# Yukari_3_9150.net
KiCad netlist of a schematic drawn in EAGLE
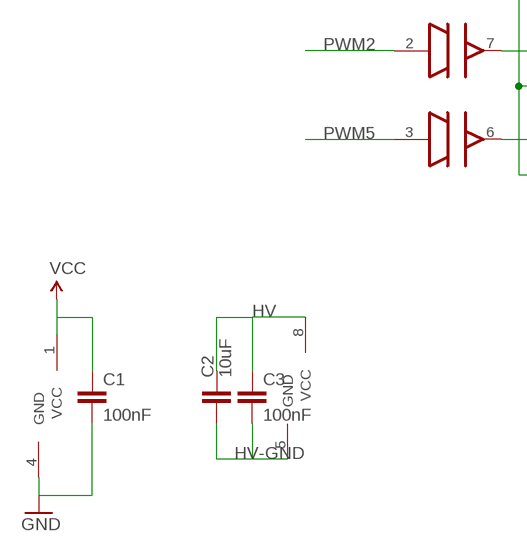
[diagram p0: schematic, sheet 1, part 1 of 2]
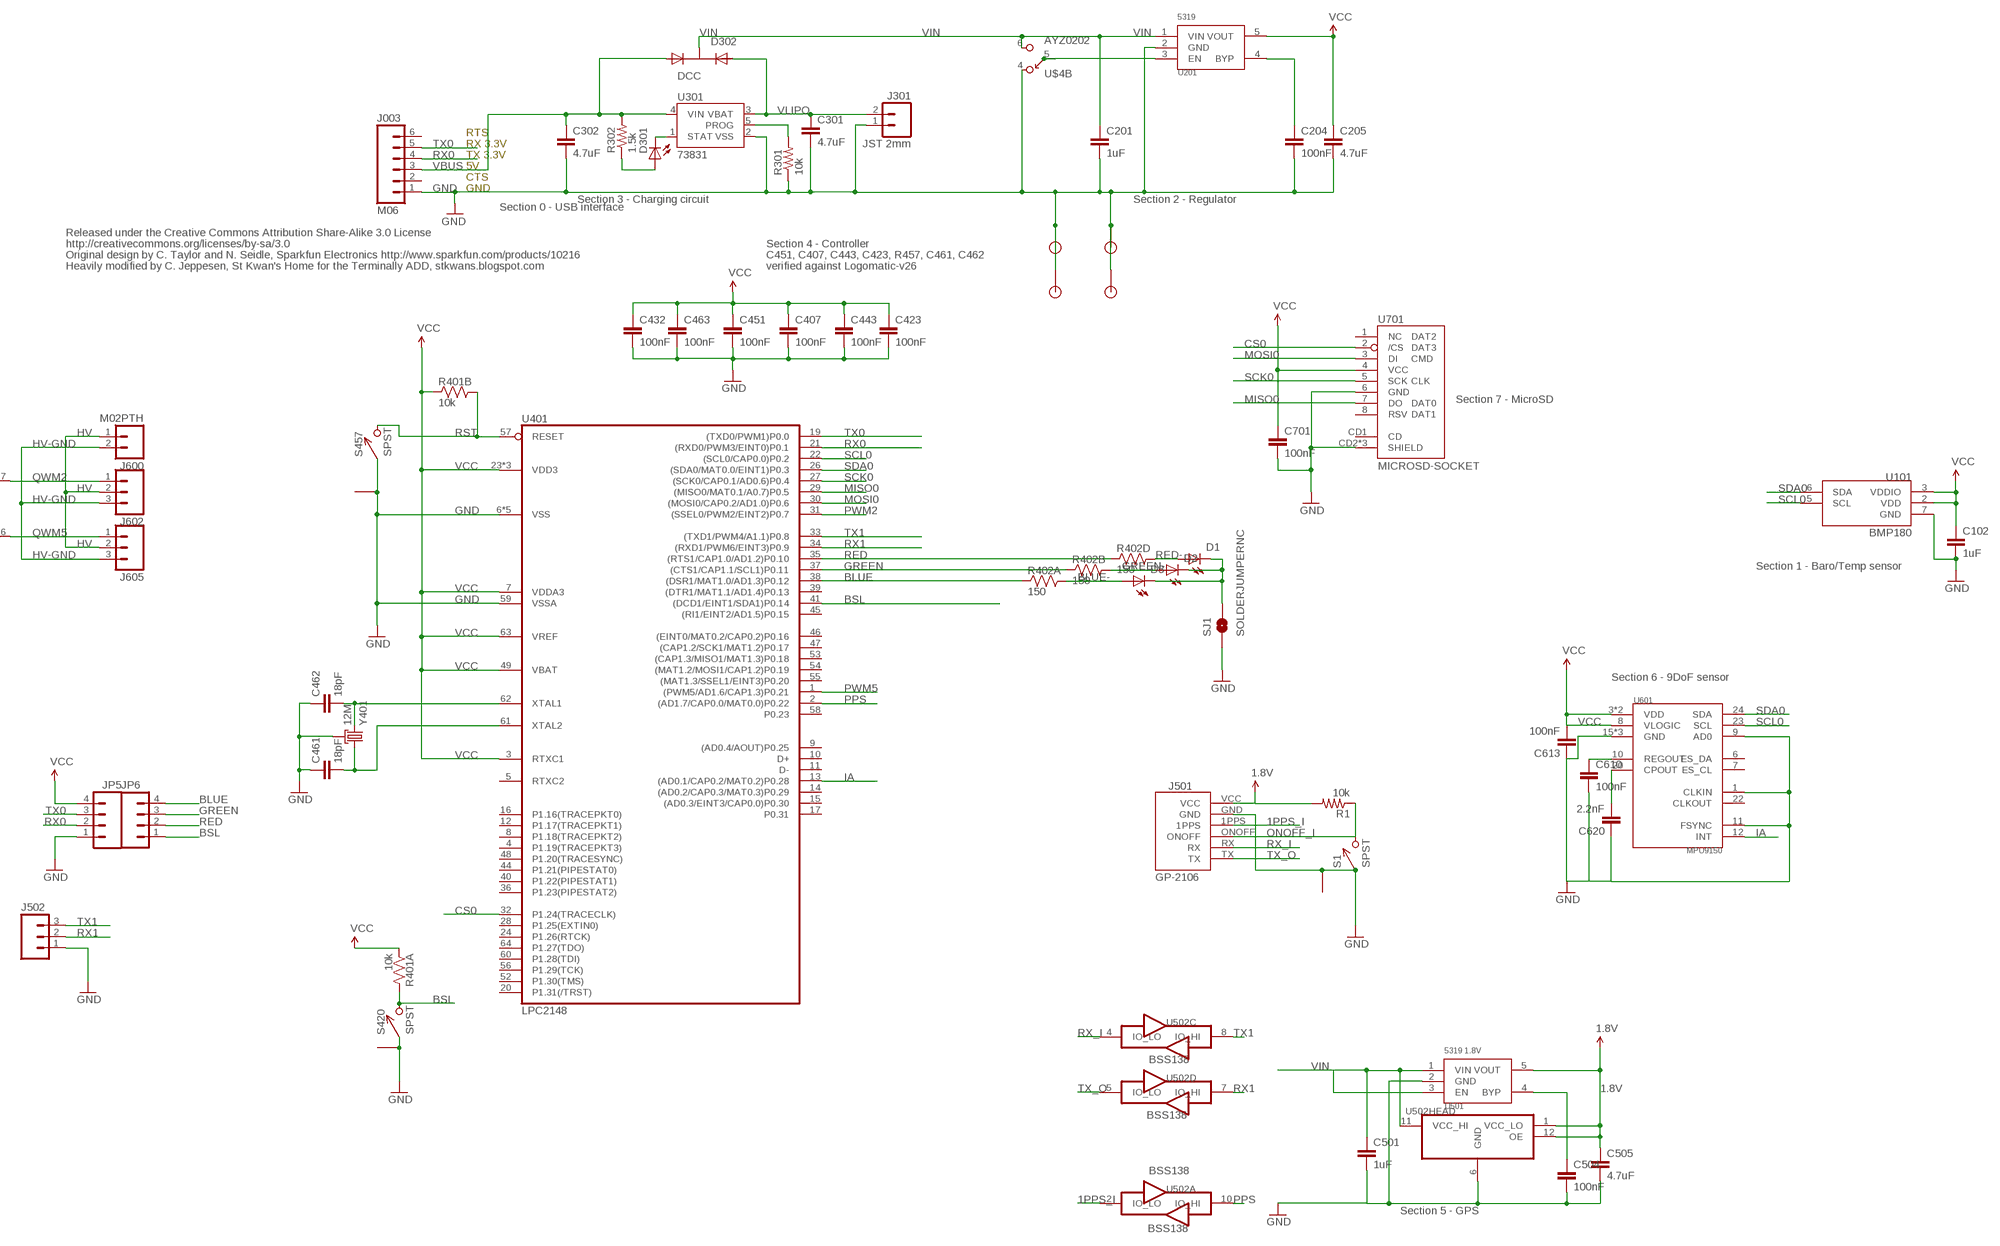
[diagram p1: schematic, sheet 1, part 2 of 2]

(export (version "E")
  (design (tool "Eeschema 10.0.6"))
  (components
    (comp (ref "C1")
      (value "100nF")
      (footprint "eagle-import:0402-CAP")
      (libsource (lib "eagle-import") (part "CAP0402-CAP"))
    )
    (comp (ref "C2")
      (value "10uF")
      (footprint "eagle-import:0603-CAP")
      (libsource (lib "eagle-import") (part "CAP0603-CAP"))
    )
    (comp (ref "C3")
      (value "100nF")
      (footprint "eagle-import:0402-CAP")
      (libsource (lib "eagle-import") (part "CAP0402-CAP"))
    )
    (comp (ref "C102")
      (value "1uF")
      (footprint "eagle-import:0402-CAP")
      (libsource (lib "eagle-import") (part "SparkFun-Passives_CAP0402-CAP"))
    )
    (comp (ref "C201")
      (value "1uF")
      (footprint "eagle-import:0402-CAP")
      (libsource (lib "eagle-import") (part "CAP0402-CAP"))
    )
    (comp (ref "C204")
      (value "100nF")
      (footprint "eagle-import:0402-CAP")
      (libsource (lib "eagle-import") (part "CAP0402-CAP"))
    )
    (comp (ref "C205")
      (value "4.7uF")
      (footprint "eagle-import:0402-CAP")
      (libsource (lib "eagle-import") (part "CAP0402-CAP"))
    )
    (comp (ref "C301")
      (value "4.7uF")
      (footprint "eagle-import:0402-CAP")
      (libsource (lib "eagle-import") (part "CAP0402-CAP"))
    )
    (comp (ref "C302")
      (value "4.7uF")
      (footprint "eagle-import:0402-CAP")
      (libsource (lib "eagle-import") (part "CAP0402-CAP"))
    )
    (comp (ref "C407")
      (value "100nF")
      (footprint "eagle-import:0402-CAP")
      (libsource (lib "eagle-import") (part "CAP0402-CAP"))
    )
    (comp (ref "C423")
      (value "100nF")
      (footprint "eagle-import:0402-CAP")
      (libsource (lib "eagle-import") (part "CAP0402-CAP"))
    )
    (comp (ref "C432")
      (value "100nF")
      (footprint "eagle-import:0402-CAP")
      (libsource (lib "eagle-import") (part "CAP0402-CAP"))
    )
    (comp (ref "C443")
      (value "100nF")
      (footprint "eagle-import:0402-CAP")
      (libsource (lib "eagle-import") (part "CAP0402-CAP"))
    )
    (comp (ref "C451")
      (value "100nF")
      (footprint "eagle-import:0402-CAP")
      (libsource (lib "eagle-import") (part "CAP0402-CAP"))
    )
    (comp (ref "C461")
      (value "18pF")
      (footprint "eagle-import:0402-CAP")
      (libsource (lib "eagle-import") (part "CAP0402-CAP"))
    )
    (comp (ref "C462")
      (value "18pF")
      (footprint "eagle-import:0402-CAP")
      (libsource (lib "eagle-import") (part "CAP0402-CAP"))
    )
    (comp (ref "C463")
      (value "100nF")
      (footprint "eagle-import:0402-CAP")
      (libsource (lib "eagle-import") (part "CAP0402-CAP"))
    )
    (comp (ref "C501")
      (value "1uF")
      (footprint "eagle-import:0402-CAP")
      (libsource (lib "eagle-import") (part "CAP0402-CAP"))
    )
    (comp (ref "C504")
      (value "100nF")
      (footprint "eagle-import:0402-CAP")
      (libsource (lib "eagle-import") (part "CAP0402-CAP"))
    )
    (comp (ref "C505")
      (value "4.7uF")
      (footprint "eagle-import:0402-CAP")
      (libsource (lib "eagle-import") (part "CAP0402-CAP"))
    )
    (comp (ref "C610")
      (value "100nF")
      (footprint "eagle-import:0402-CAP")
      (libsource (lib "eagle-import") (part "SparkFun-Passives_CAP0402-CAP"))
    )
    (comp (ref "C613")
      (value "100nF")
      (footprint "eagle-import:0402-CAP")
      (libsource (lib "eagle-import") (part "SparkFun-Passives_CAP0402-CAP"))
    )
    (comp (ref "C620")
      (value "2.2nF")
      (footprint "eagle-import:0402-CAP")
      (libsource (lib "eagle-import") (part "SparkFun-Passives_CAP0402-CAP"))
    )
    (comp (ref "C701")
      (value "100nF")
      (footprint "eagle-import:0402-CAP")
      (libsource (lib "eagle-import") (part "CAP0402-CAP"))
    )
    (comp (ref "D1")
      (value "RED")
      (footprint "eagle-import:LED-0603")
      (libsource (lib "eagle-import") (part "LED0603"))
    )
    (comp (ref "D2")
      (value "GREEN")
      (footprint "eagle-import:LED-0603")
      (libsource (lib "eagle-import") (part "LED0603"))
    )
    (comp (ref "D3")
      (value "BLUE")
      (footprint "eagle-import:LED-0603")
      (libsource (lib "eagle-import") (part "LED0603"))
    )
    (comp (ref "D301")
      (value "RED")
      (footprint "eagle-import:LED-0603")
      (libsource (lib "eagle-import") (part "LED0603"))
    )
    (comp (ref "D302")
      (value "DCC")
      (footprint "eagle-import:SOT-23-3")
      (libsource (lib "eagle-import") (part "PMEG2005CT"))
    )
    (comp (ref "J003")
      (value "M06")
      (footprint "eagle-import:1X06")
      (libsource (lib "eagle-import") (part "M06SIP"))
    )
    (comp (ref "J301")
      (value "JST 2mm")
      (footprint "eagle-import:JST-2-SMD")
      (libsource (lib "eagle-import") (part "M02-JST-2MM-SMT"))
    )
    (comp (ref "J501")
      (value "GP-2106")
      (footprint "eagle-import:GP-2106")
      (libsource (lib "eagle-import") (part "GP-2106"))
    )
    (comp (ref "J502")
      (value "M03PTH")
      (footprint "eagle-import:1X03")
      (libsource (lib "eagle-import") (part "M03PTH"))
    )
    (comp (ref "J600")
      (value "M02PTH")
      (footprint "eagle-import:1X02")
      (libsource (lib "eagle-import") (part "SparkFun-Connectors_M02PTH"))
    )
    (comp (ref "J602")
      (value "M03PTH")
      (footprint "eagle-import:1X03")
      (libsource (lib "eagle-import") (part "M03PTH"))
    )
    (comp (ref "J605")
      (value "M03PTH")
      (footprint "eagle-import:1X03")
      (libsource (lib "eagle-import") (part "M03PTH"))
    )
    (comp (ref "JP1")
      (value "STANDOFF")
      (footprint "eagle-import:STANDOFF")
      (libsource (lib "eagle-import") (part "STANDOFF"))
    )
    (comp (ref "JP2")
      (value "STANDOFF")
      (footprint "eagle-import:STANDOFF")
      (libsource (lib "eagle-import") (part "STANDOFF"))
    )
    (comp (ref "JP3")
      (value "STANDOFF")
      (footprint "eagle-import:STANDOFF")
      (libsource (lib "eagle-import") (part "STANDOFF"))
    )
    (comp (ref "JP4")
      (value "STANDOFF")
      (footprint "eagle-import:STANDOFF")
      (libsource (lib "eagle-import") (part "STANDOFF"))
    )
    (comp (ref "JP5")
      (value "M04PTH")
      (footprint "eagle-import:1X04")
      (libsource (lib "eagle-import") (part "M04PTH"))
    )
    (comp (ref "JP6")
      (value "M04PTH")
      (footprint "eagle-import:1X04")
      (libsource (lib "eagle-import") (part "M04PTH"))
    )
    (comp (ref "R1")
      (value "10k")
      (footprint "eagle-import:0402-RES")
      (libsource (lib "eagle-import") (part "RESISTOR0402-RES"))
    )
    (comp (ref "R301")
      (value "10k")
      (footprint "eagle-import:0402-RES")
      (libsource (lib "eagle-import") (part "RESISTOR0402-RES"))
    )
    (comp (ref "R302")
      (value "1.5k")
      (footprint "eagle-import:0402-RES")
      (libsource (lib "eagle-import") (part "RESISTOR0402-RES"))
    )
    (comp (ref "R401")
      (value "10k")
      (footprint "eagle-import:CRA02")
      (libsource (lib "eagle-import") (part "RP2EXB24V"))
    )
    (comp (ref "R402")
      (value "150")
      (footprint "eagle-import:CRA04")
      (libsource (lib "eagle-import") (part "RP404"))
    )
    (comp (ref "S1")
      (value "SPST")
      (footprint "eagle-import:B3U-1100P")
      (libsource (lib "eagle-import") (part "B3U-1100P"))
    )
    (comp (ref "S420")
      (value "SPST")
      (footprint "eagle-import:B3U-1100P")
      (libsource (lib "eagle-import") (part "B3U-1100P"))
    )
    (comp (ref "S457")
      (value "SPST")
      (footprint "eagle-import:B3U-1100P")
      (libsource (lib "eagle-import") (part "B3U-1100P"))
    )
    (comp (ref "SJ1")
      (value "SOLDERJUMPERNC")
      (footprint "eagle-import:SJ_2S")
      (libsource (lib "eagle-import") (part "SOLDERJUMPERNC"))
    )
    (comp (ref "U$4")
      (value "AYZ0202")
      (footprint "eagle-import:AYZ0202")
      (libsource (lib "eagle-import") (part "AYZ0202"))
    )
    (comp (ref "U101")
      (value "BMP180")
      (footprint "eagle-import:BMP180")
      (libsource (lib "eagle-import") (part "BMP180"))
    )
    (comp (ref "U201")
      (value "5319")
      (footprint "eagle-import:SOT-23-5")
      (libsource (lib "eagle-import") (part "MIC5319D5"))
    )
    (comp (ref "U301")
      (value "73831")
      (footprint "eagle-import:SOT23-5")
      (libsource (lib "eagle-import") (part "MCP73831"))
    )
    (comp (ref "U401")
      (value "LPC2148")
      (footprint "eagle-import:LQFP64")
      (libsource (lib "eagle-import") (part "LPC2148"))
    )
    (comp (ref "U501")
      (value "5319 1.8V")
      (footprint "eagle-import:SOT-23-5")
      (libsource (lib "eagle-import") (part "MIC5319D5"))
    )
    (comp (ref "U502")
      (value "TXB0104RUT")
      (footprint "eagle-import:R-PUQFN-N12")
      (libsource (lib "eagle-import") (part "TXB0104RUT"))
    )
    (comp (ref "U600")
      (value "ADUM3221")
      (footprint "eagle-import:SO8N")
      (libsource (lib "eagle-import") (part "ADUM3221"))
    )
    (comp (ref "U601")
      (value "MPU9150")
      (footprint "eagle-import:LLGA24")
      (libsource (lib "eagle-import") (part "MPU9150"))
    )
    (comp (ref "U701")
      (value "MICROSD-SOCKET")
      (footprint "eagle-import:MICROSD-SOCKET-PP")
      (libsource (lib "eagle-import") (part "MICROSD-SOCKET"))
    )
    (comp (ref "Y401")
      (value "12M")
      (footprint "eagle-import:CRYSTAL_SMD")
      (libsource (lib "eagle-import") (part "TSX-3225"))
    )
  )
  (nets
    (net (code "1") (name "/1PPS_I") (class "Default")
      (node (ref "J501") (pin "1PPS") (pinfunction "1PPS_1PPS") (pintype "bidirectional"))
      (node (ref "U502") (pin "2") (pinfunction "IO_LO_2") (pintype "bidirectional"))
    )
    (net (code "2") (name "/BLUE") (class "Default")
      (node (ref "JP6") (pin "4") (pinfunction "4_4") (pintype "passive"))
      (node (ref "R402") (pin "1") (pinfunction "1_1") (pintype "passive"))
      (node (ref "U401") (pin "38") (pinfunction "(DSR1/MAT1.0/AD1.3)P0.12_38") (pintype "bidirectional"))
    )
    (net (code "3") (name "/BLUE-") (class "Default")
      (node (ref "D3") (pin "A") (pinfunction "A_A") (pintype "passive"))
      (node (ref "R402") (pin "8") (pinfunction "2_8") (pintype "passive"))
    )
    (net (code "4") (name "/BSL") (class "Default")
      (node (ref "JP6") (pin "1") (pinfunction "1_1") (pintype "passive"))
      (node (ref "R401") (pin "4") (pinfunction "2_4") (pintype "passive"))
      (node (ref "S420") (pin "P$2") (pinfunction "2_P$2") (pintype "bidirectional"))
      (node (ref "U401") (pin "41") (pinfunction "(DCD1/EINT1/SDA1)P0.14_41") (pintype "bidirectional"))
    )
    (net (code "5") (name "/CS0") (class "Default")
      (node (ref "U401") (pin "32") (pinfunction "P1.24(TRACECLK)_32") (pintype "bidirectional"))
      (node (ref "U701") (pin "2") (pinfunction "/CS_2") (pintype "bidirectional"))
    )
    (net (code "6") (name "/GREEN") (class "Default")
      (node (ref "JP6") (pin "3") (pinfunction "3_3") (pintype "passive"))
      (node (ref "R402") (pin "2") (pinfunction "1_2") (pintype "passive"))
      (node (ref "U401") (pin "37") (pinfunction "(CTS1/CAP1.1/SCL1)P0.11_37") (pintype "bidirectional"))
    )
    (net (code "7") (name "/GREEN-") (class "Default")
      (node (ref "D2") (pin "A") (pinfunction "A_A") (pintype "passive"))
      (node (ref "R402") (pin "7") (pinfunction "2_7") (pintype "passive"))
    )
    (net (code "8") (name "/HV") (class "Default")
      (node (ref "C2") (pin "1") (pinfunction "1_1") (pintype "passive"))
      (node (ref "C3") (pin "1") (pinfunction "1_1") (pintype "passive"))
      (node (ref "J600") (pin "1") (pinfunction "1_1") (pintype "passive"))
      (node (ref "J602") (pin "2") (pinfunction "2_2") (pintype "passive"))
      (node (ref "J605") (pin "2") (pinfunction "2_2") (pintype "passive"))
      (node (ref "U600") (pin "8") (pinfunction "VCC_8") (pintype "bidirectional"))
    )
    (net (code "9") (name "/HV-GND") (class "Default")
      (node (ref "C2") (pin "2") (pinfunction "2_2") (pintype "passive"))
      (node (ref "C3") (pin "2") (pinfunction "2_2") (pintype "passive"))
      (node (ref "J600") (pin "2") (pinfunction "2_2") (pintype "passive"))
      (node (ref "J602") (pin "3") (pinfunction "3_3") (pintype "passive"))
      (node (ref "J605") (pin "3") (pinfunction "3_3") (pintype "passive"))
      (node (ref "U600") (pin "5") (pinfunction "GND_5") (pintype "bidirectional"))
    )
    (net (code "10") (name "/IA") (class "Default")
      (node (ref "U401") (pin "13") (pinfunction "(AD0.1/CAP0.2/MAT0.2)P0.28_13") (pintype "bidirectional"))
      (node (ref "U601") (pin "12") (pinfunction "INT_12") (pintype "bidirectional"))
    )
    (net (code "11") (name "/MISO0") (class "Default")
      (node (ref "U401") (pin "29") (pinfunction "(MISO0/MAT0.1/A0.7)P0.5_29") (pintype "bidirectional"))
      (node (ref "U701") (pin "7") (pinfunction "DO_7") (pintype "bidirectional"))
    )
    (net (code "12") (name "/MOSI0") (class "Default")
      (node (ref "U401") (pin "30") (pinfunction "(MOSI0/CAP0.2/AD1.0)P0.6_30") (pintype "bidirectional"))
      (node (ref "U701") (pin "3") (pinfunction "DI_3") (pintype "bidirectional"))
    )
    (net (code "13") (name "/ONOFF_I") (class "Default")
      (node (ref "J501") (pin "ONOFF") (pinfunction "ONOFF_ONOFF") (pintype "bidirectional"))
      (node (ref "R1") (pin "1") (pinfunction "1_1") (pintype "passive"))
      (node (ref "S1") (pin "P$2") (pinfunction "2_P$2") (pintype "bidirectional"))
    )
    (net (code "14") (name "/PPS") (class "Default")
      (node (ref "U401") (pin "2") (pinfunction "(AD1.7/CAP0.0/MAT0.0)P0.22_2") (pintype "bidirectional"))
      (node (ref "U502") (pin "10") (pinfunction "IO_HI_10") (pintype "bidirectional"))
    )
    (net (code "15") (name "/PWM2") (class "Default")
      (node (ref "U401") (pin "31") (pinfunction "(SSEL0/PWM2/EINT2)P0.7_31") (pintype "bidirectional"))
      (node (ref "U600") (pin "2") (pinfunction "IN_2") (pintype "input"))
    )
    (net (code "16") (name "/PWM5") (class "Default")
      (node (ref "U401") (pin "1") (pinfunction "(PWM5/AD1.6/CAP1.3)P0.21_1") (pintype "bidirectional"))
      (node (ref "U600") (pin "3") (pinfunction "IN_3") (pintype "input"))
    )
    (net (code "17") (name "/QWM2") (class "Default")
      (node (ref "J602") (pin "1") (pinfunction "1_1") (pintype "passive"))
      (node (ref "U600") (pin "7") (pinfunction "OUT_7") (pintype "bidirectional"))
    )
    (net (code "18") (name "/QWM5") (class "Default")
      (node (ref "J605") (pin "1") (pinfunction "1_1") (pintype "passive"))
      (node (ref "U600") (pin "6") (pinfunction "OUT_6") (pintype "bidirectional"))
    )
    (net (code "19") (name "/RED") (class "Default")
      (node (ref "JP6") (pin "2") (pinfunction "2_2") (pintype "passive"))
      (node (ref "R402") (pin "4") (pinfunction "1_4") (pintype "passive"))
      (node (ref "U401") (pin "35") (pinfunction "(RTS1/CAP1.0/AD1.2)P0.10_35") (pintype "bidirectional"))
    )
    (net (code "20") (name "/RED-") (class "Default")
      (node (ref "D1") (pin "A") (pinfunction "A_A") (pintype "passive"))
      (node (ref "R402") (pin "5") (pinfunction "2_5") (pintype "passive"))
    )
    (net (code "21") (name "/RST") (class "Default")
      (node (ref "R401") (pin "3") (pinfunction "2_3") (pintype "passive"))
      (node (ref "S457") (pin "P$2") (pinfunction "2_P$2") (pintype "bidirectional"))
      (node (ref "U401") (pin "57") (pinfunction "RESET_57") (pintype "input"))
    )
    (net (code "22") (name "/RX0") (class "Default")
      (node (ref "J003") (pin "4") (pinfunction "4_4") (pintype "passive"))
      (node (ref "JP5") (pin "2") (pinfunction "2_2") (pintype "passive"))
      (node (ref "U401") (pin "21") (pinfunction "(RXD0/PWM3/EINT0)P0.1_21") (pintype "bidirectional"))
    )
    (net (code "23") (name "/RX1") (class "Default")
      (node (ref "J502") (pin "2") (pinfunction "2_2") (pintype "passive"))
      (node (ref "U401") (pin "34") (pinfunction "(RXD1/PWM6/EINT3)P0.9_34") (pintype "bidirectional"))
      (node (ref "U502") (pin "7") (pinfunction "IO_HI_7") (pintype "bidirectional"))
    )
    (net (code "24") (name "/RX_I") (class "Default")
      (node (ref "J501") (pin "RX") (pinfunction "RX_RX") (pintype "bidirectional"))
      (node (ref "U502") (pin "4") (pinfunction "IO_LO_4") (pintype "bidirectional"))
    )
    (net (code "25") (name "/SCK0") (class "Default")
      (node (ref "U401") (pin "27") (pinfunction "(SCK0/CAP0.1/AD0.6)P0.4_27") (pintype "bidirectional"))
      (node (ref "U701") (pin "5") (pinfunction "SCK_5") (pintype "bidirectional"))
    )
    (net (code "26") (name "/SCL0") (class "Default")
      (node (ref "U101") (pin "5") (pinfunction "SCL_5") (pintype "input"))
      (node (ref "U401") (pin "22") (pinfunction "(SCL0/CAP0.0)P0.2_22") (pintype "bidirectional"))
      (node (ref "U601") (pin "23") (pinfunction "SCL_23") (pintype "bidirectional"))
    )
    (net (code "27") (name "/SDA0") (class "Default")
      (node (ref "U101") (pin "6") (pinfunction "SDA_6") (pintype "bidirectional"))
      (node (ref "U401") (pin "26") (pinfunction "(SDA0/MAT0.0/EINT1)P0.3_26") (pintype "bidirectional"))
      (node (ref "U601") (pin "24") (pinfunction "SDA_24") (pintype "bidirectional"))
    )
    (net (code "28") (name "/TX0") (class "Default")
      (node (ref "J003") (pin "5") (pinfunction "5_5") (pintype "passive"))
      (node (ref "JP5") (pin "3") (pinfunction "3_3") (pintype "passive"))
      (node (ref "U401") (pin "19") (pinfunction "(TXD0/PWM1)P0.0_19") (pintype "bidirectional"))
    )
    (net (code "29") (name "/TX1") (class "Default")
      (node (ref "J502") (pin "3") (pinfunction "3_3") (pintype "passive"))
      (node (ref "U401") (pin "33") (pinfunction "(TXD1/PWM4/A1.1)P0.8_33") (pintype "bidirectional"))
      (node (ref "U502") (pin "8") (pinfunction "IO_HI_8") (pintype "bidirectional"))
    )
    (net (code "30") (name "/TX_O") (class "Default")
      (node (ref "J501") (pin "TX") (pinfunction "TX_TX") (pintype "bidirectional"))
      (node (ref "U502") (pin "5") (pinfunction "IO_LO_5") (pintype "bidirectional"))
    )
    (net (code "31") (name "/VBUS") (class "Default")
      (node (ref "C302") (pin "1") (pinfunction "1_1") (pintype "passive"))
      (node (ref "D302") (pin "1") (pinfunction "A1_1") (pintype "passive"))
      (node (ref "J003") (pin "3") (pinfunction "3_3") (pintype "passive"))
      (node (ref "R302") (pin "2") (pinfunction "2_2") (pintype "passive"))
      (node (ref "U301") (pin "4") (pinfunction "VIN_4") (pintype "power_in"))
    )
    (net (code "32") (name "/VIN") (class "Default")
      (node (ref "C201") (pin "1") (pinfunction "1_1") (pintype "passive"))
      (node (ref "C501") (pin "1") (pinfunction "1_1") (pintype "passive"))
      (node (ref "D302") (pin "3") (pinfunction "K_3") (pintype "passive"))
      (node (ref "U$4") (pin "6") (pinfunction "P$2_6") (pintype "bidirectional"))
      (node (ref "U201") (pin "1") (pinfunction "VIN_1") (pintype "bidirectional"))
      (node (ref "U501") (pin "1") (pinfunction "VIN_1") (pintype "bidirectional"))
      (node (ref "U501") (pin "3") (pinfunction "EN_3") (pintype "bidirectional"))
      (node (ref "U502") (pin "11") (pinfunction "VCC_HI_11") (pintype "power_in"))
    )
    (net (code "33") (name "/VLIPO") (class "Default")
      (node (ref "C301") (pin "1") (pinfunction "1_1") (pintype "passive"))
      (node (ref "D302") (pin "2") (pinfunction "A2_2") (pintype "passive"))
      (node (ref "J301") (pin "2") (pinfunction "2_2") (pintype "passive"))
      (node (ref "U301") (pin "3") (pinfunction "VBAT_3") (pintype "power_in"))
    )
    (net (code "34") (name "1.8V") (class "Default")
      (node (ref "C505") (pin "1") (pinfunction "1_1") (pintype "passive"))
      (node (ref "J501") (pin "VCC") (pinfunction "VCC_VCC") (pintype "bidirectional"))
      (node (ref "R1") (pin "2") (pinfunction "2_2") (pintype "passive"))
      (node (ref "U501") (pin "5") (pinfunction "VOUT_5") (pintype "bidirectional"))
      (node (ref "U502") (pin "1") (pinfunction "VCC_LO_1") (pintype "power_in"))
      (node (ref "U502") (pin "12") (pinfunction "OE_12") (pintype "bidirectional"))
    )
    (net (code "35") (name "GND") (class "Default")
      (node (ref "C1") (pin "2") (pinfunction "2_2") (pintype "passive"))
      (node (ref "C102") (pin "2") (pinfunction "2_2") (pintype "passive"))
      (node (ref "C201") (pin "2") (pinfunction "2_2") (pintype "passive"))
      (node (ref "C204") (pin "2") (pinfunction "2_2") (pintype "passive"))
      (node (ref "C205") (pin "2") (pinfunction "2_2") (pintype "passive"))
      (node (ref "C301") (pin "2") (pinfunction "2_2") (pintype "passive"))
      (node (ref "C302") (pin "2") (pinfunction "2_2") (pintype "passive"))
      (node (ref "C407") (pin "2") (pinfunction "2_2") (pintype "passive"))
      (node (ref "C423") (pin "2") (pinfunction "2_2") (pintype "passive"))
      (node (ref "C432") (pin "2") (pinfunction "2_2") (pintype "passive"))
      (node (ref "C443") (pin "2") (pinfunction "2_2") (pintype "passive"))
      (node (ref "C451") (pin "2") (pinfunction "2_2") (pintype "passive"))
      (node (ref "C461") (pin "1") (pinfunction "1_1") (pintype "passive"))
      (node (ref "C462") (pin "1") (pinfunction "1_1") (pintype "passive"))
      (node (ref "C463") (pin "2") (pinfunction "2_2") (pintype "passive"))
      (node (ref "C501") (pin "2") (pinfunction "2_2") (pintype "passive"))
      (node (ref "C504") (pin "2") (pinfunction "2_2") (pintype "passive"))
      (node (ref "C505") (pin "2") (pinfunction "2_2") (pintype "passive"))
      (node (ref "C610") (pin "2") (pinfunction "2_2") (pintype "passive"))
      (node (ref "C613") (pin "1") (pinfunction "1_1") (pintype "passive"))
      (node (ref "C620") (pin "1") (pinfunction "1_1") (pintype "passive"))
      (node (ref "C701") (pin "2") (pinfunction "2_2") (pintype "passive"))
      (node (ref "J003") (pin "1") (pinfunction "1_1") (pintype "passive"))
      (node (ref "J301") (pin "1") (pinfunction "1_1") (pintype "passive"))
      (node (ref "J501") (pin "GND") (pinfunction "GND_GND") (pintype "bidirectional"))
      (node (ref "J502") (pin "1") (pinfunction "1_1") (pintype "passive"))
      (node (ref "JP1") (pin "P$1") (pinfunction "P$1_P$1") (pintype "bidirectional"))
      (node (ref "JP2") (pin "P$1") (pinfunction "P$1_P$1") (pintype "bidirectional"))
      (node (ref "JP3") (pin "P$1") (pinfunction "P$1_P$1") (pintype "bidirectional"))
      (node (ref "JP4") (pin "P$1") (pinfunction "P$1_P$1") (pintype "bidirectional"))
      (node (ref "JP5") (pin "1") (pinfunction "1_1") (pintype "passive"))
      (node (ref "R301") (pin "1") (pinfunction "1_1") (pintype "passive"))
      (node (ref "S1") (pin "P$1") (pinfunction "1_P$1") (pintype "bidirectional"))
      (node (ref "S1") (pin "P$3") (pinfunction "1_P$3") (pintype "bidirectional"))
      (node (ref "S420") (pin "P$1") (pinfunction "1_P$1") (pintype "bidirectional"))
      (node (ref "S420") (pin "P$3") (pinfunction "1_P$3") (pintype "bidirectional"))
      (node (ref "S457") (pin "P$1") (pinfunction "1_P$1") (pintype "bidirectional"))
      (node (ref "S457") (pin "P$3") (pinfunction "1_P$3") (pintype "bidirectional"))
      (node (ref "SJ1") (pin "1") (pinfunction "1_1") (pintype "passive"))
      (node (ref "U$4") (pin "4") (pinfunction "P$1_4") (pintype "bidirectional"))
      (node (ref "U101") (pin "7") (pinfunction "GND_7") (pintype "power_in"))
      (node (ref "U201") (pin "2") (pinfunction "GND_2") (pintype "bidirectional"))
      (node (ref "U301") (pin "2") (pinfunction "VSS_2") (pintype "power_in"))
      (node (ref "U401") (pin "18") (pinfunction "VSS_18") (pintype "power_in"))
      (node (ref "U401") (pin "25") (pinfunction "VSS_25") (pintype "power_in"))
      (node (ref "U401") (pin "42") (pinfunction "VSS_42") (pintype "power_in"))
      (node (ref "U401") (pin "50") (pinfunction "VSS_50") (pintype "power_in"))
      (node (ref "U401") (pin "59") (pinfunction "VSSA_59") (pintype "power_in"))
      (node (ref "U401") (pin "6") (pinfunction "VSS_6") (pintype "power_in"))
      (node (ref "U501") (pin "2") (pinfunction "GND_2") (pintype "bidirectional"))
      (node (ref "U502") (pin "6") (pinfunction "GND_6") (pintype "power_in"))
      (node (ref "U600") (pin "4") (pinfunction "GND_4") (pintype "bidirectional"))
      (node (ref "U601") (pin "1") (pinfunction "CLKIN_1") (pintype "bidirectional"))
      (node (ref "U601") (pin "11") (pinfunction "FSYNC_11") (pintype "bidirectional"))
      (node (ref "U601") (pin "15") (pinfunction "GND_15") (pintype "bidirectional"))
      (node (ref "U601") (pin "17") (pinfunction "GND_17") (pintype "bidirectional"))
      (node (ref "U601") (pin "18") (pinfunction "GND_18") (pintype "bidirectional"))
      (node (ref "U601") (pin "9") (pinfunction "AD0_9") (pintype "bidirectional"))
      (node (ref "U701") (pin "6") (pinfunction "GND_6") (pintype "bidirectional"))
      (node (ref "U701") (pin "CD2") (pinfunction "SHIELD_CD2") (pintype "bidirectional"))
      (node (ref "U701") (pin "GND1") (pinfunction "SHIELD_GND1") (pintype "bidirectional"))
      (node (ref "U701") (pin "GND3") (pinfunction "SHIELD_GND3") (pintype "bidirectional"))
      (node (ref "Y401") (pin "2") (pinfunction "GND_2") (pintype "passive"))
      (node (ref "Y401") (pin "4") (pinfunction "GND_4") (pintype "passive"))
    )
    (net (code "36") (name "Net-(D1-PadC)") (class "Default")
      (node (ref "D1") (pin "C") (pinfunction "C_C") (pintype "passive"))
      (node (ref "D2") (pin "C") (pinfunction "C_C") (pintype "passive"))
      (node (ref "D3") (pin "C") (pinfunction "C_C") (pintype "passive"))
      (node (ref "SJ1") (pin "2") (pinfunction "2_2") (pintype "passive"))
    )
    (net (code "37") (name "Net-(D301-PadA)") (class "Default")
      (node (ref "D301") (pin "A") (pinfunction "A_A") (pintype "passive"))
      (node (ref "R302") (pin "1") (pinfunction "1_1") (pintype "passive"))
    )
    (net (code "38") (name "Net-(U$4B-P$3)") (class "Default")
      (node (ref "U$4") (pin "5") (pinfunction "P$3_5") (pintype "bidirectional"))
      (node (ref "U201") (pin "3") (pinfunction "EN_3") (pintype "bidirectional"))
    )
    (net (code "39") (name "Net-(U201-BYP)") (class "Default")
      (node (ref "C204") (pin "1") (pinfunction "1_1") (pintype "passive"))
      (node (ref "U201") (pin "4") (pinfunction "BYP_4") (pintype "bidirectional"))
    )
    (net (code "40") (name "Net-(U301-PROG)") (class "Default")
      (node (ref "R301") (pin "2") (pinfunction "2_2") (pintype "passive"))
      (node (ref "U301") (pin "5") (pinfunction "PROG_5") (pintype "input"))
    )
    (net (code "41") (name "Net-(U301-STAT)") (class "Default")
      (node (ref "D301") (pin "C") (pinfunction "C_C") (pintype "passive"))
      (node (ref "U301") (pin "1") (pinfunction "STAT_1") (pintype "output"))
    )
    (net (code "42") (name "Net-(U401-XTAL1)") (class "Default")
      (node (ref "C462") (pin "2") (pinfunction "2_2") (pintype "passive"))
      (node (ref "U401") (pin "62") (pinfunction "XTAL1_62") (pintype "input"))
      (node (ref "Y401") (pin "3") (pinfunction "2_3") (pintype "passive"))
    )
    (net (code "43") (name "Net-(U401-XTAL2)") (class "Default")
      (node (ref "C461") (pin "2") (pinfunction "2_2") (pintype "passive"))
      (node (ref "U401") (pin "61") (pinfunction "XTAL2_61") (pintype "output"))
      (node (ref "Y401") (pin "1") (pinfunction "1_1") (pintype "passive"))
    )
    (net (code "44") (name "Net-(U501-BYP)") (class "Default")
      (node (ref "C504") (pin "1") (pinfunction "1_1") (pintype "passive"))
      (node (ref "U501") (pin "4") (pinfunction "BYP_4") (pintype "bidirectional"))
    )
    (net (code "45") (name "Net-(U601-CPOUT)") (class "Default")
      (node (ref "C620") (pin "2") (pinfunction "2_2") (pintype "passive"))
      (node (ref "U601") (pin "20") (pinfunction "CPOUT_20") (pintype "bidirectional"))
    )
    (net (code "46") (name "Net-(U601-REGOUT)") (class "Default")
      (node (ref "C610") (pin "1") (pinfunction "1_1") (pintype "passive"))
      (node (ref "U601") (pin "10") (pinfunction "REGOUT_10") (pintype "bidirectional"))
    )
    (net (code "47") (name "VCC") (class "Default")
      (node (ref "C1") (pin "1") (pinfunction "1_1") (pintype "passive"))
      (node (ref "C102") (pin "1") (pinfunction "1_1") (pintype "passive"))
      (node (ref "C205") (pin "1") (pinfunction "1_1") (pintype "passive"))
      (node (ref "C407") (pin "1") (pinfunction "1_1") (pintype "passive"))
      (node (ref "C423") (pin "1") (pinfunction "1_1") (pintype "passive"))
      (node (ref "C432") (pin "1") (pinfunction "1_1") (pintype "passive"))
      (node (ref "C443") (pin "1") (pinfunction "1_1") (pintype "passive"))
      (node (ref "C451") (pin "1") (pinfunction "1_1") (pintype "passive"))
      (node (ref "C463") (pin "1") (pinfunction "1_1") (pintype "passive"))
      (node (ref "C613") (pin "2") (pinfunction "2_2") (pintype "passive"))
      (node (ref "C701") (pin "1") (pinfunction "1_1") (pintype "passive"))
      (node (ref "JP5") (pin "4") (pinfunction "4_4") (pintype "passive"))
      (node (ref "R401") (pin "1") (pinfunction "1_1") (pintype "passive"))
      (node (ref "R401") (pin "2") (pinfunction "1_2") (pintype "passive"))
      (node (ref "U101") (pin "2") (pinfunction "VDD_2") (pintype "power_in"))
      (node (ref "U101") (pin "3") (pinfunction "VDDIO_3") (pintype "power_in"))
      (node (ref "U201") (pin "5") (pinfunction "VOUT_5") (pintype "bidirectional"))
      (node (ref "U401") (pin "23") (pinfunction "VDD3_23") (pintype "power_in"))
      (node (ref "U401") (pin "3") (pinfunction "RTXC1_3") (pintype "input"))
      (node (ref "U401") (pin "43") (pinfunction "VDD3_43") (pintype "power_in"))
      (node (ref "U401") (pin "49") (pinfunction "VBAT_49") (pintype "power_in"))
      (node (ref "U401") (pin "51") (pinfunction "VDD3_51") (pintype "power_in"))
      (node (ref "U401") (pin "63") (pinfunction "VREF_63") (pintype "input"))
      (node (ref "U401") (pin "7") (pinfunction "VDDA3_7") (pintype "power_in"))
      (node (ref "U600") (pin "1") (pinfunction "VCC_1") (pintype "bidirectional"))
      (node (ref "U601") (pin "13") (pinfunction "VDD_13") (pintype "bidirectional"))
      (node (ref "U601") (pin "3") (pinfunction "VDD_3") (pintype "bidirectional"))
      (node (ref "U601") (pin "8") (pinfunction "VLOGIC_8") (pintype "bidirectional"))
      (node (ref "U701") (pin "4") (pinfunction "VCC_4") (pintype "bidirectional"))
    )
    (net (code "48") (name "unconnected-(J003-Pad2)") (class "Default")
      (node (ref "J003") (pin "2") (pinfunction "2_2") (pintype "passive"))
    )
    (net (code "49") (name "unconnected-(J003-Pad6)") (class "Default")
      (node (ref "J003") (pin "6") (pinfunction "6_6") (pintype "passive"))
    )
    (net (code "50") (name "unconnected-(U401-(AD0.2{slash}CAP0.3{slash}MAT0.3)P0.29-Pad14)") (class "Default")
      (node (ref "U401") (pin "14") (pinfunction "(AD0.2/CAP0.3/MAT0.3)P0.29_14") (pintype "bidirectional"))
    )
    (net (code "51") (name "unconnected-(U401-(AD0.3{slash}EINT3{slash}CAP0.0)P0.30-Pad15)") (class "Default")
      (node (ref "U401") (pin "15") (pinfunction "(AD0.3/EINT3/CAP0.0)P0.30_15") (pintype "bidirectional"))
    )
    (net (code "52") (name "unconnected-(U401-(AD0.4{slash}AOUT)P0.25-Pad9)") (class "Default")
      (node (ref "U401") (pin "9") (pinfunction "(AD0.4/AOUT)P0.25_9") (pintype "bidirectional"))
    )
    (net (code "53") (name "unconnected-(U401-(CAP1.2{slash}SCK1{slash}MAT1.2)P0.17-Pad47)") (class "Default")
      (node (ref "U401") (pin "47") (pinfunction "(CAP1.2/SCK1/MAT1.2)P0.17_47") (pintype "bidirectional"))
    )
    (net (code "54") (name "unconnected-(U401-(CAP1.3{slash}MISO1{slash}MAT1.3)P0.18-Pad53)") (class "Default")
      (node (ref "U401") (pin "53") (pinfunction "(CAP1.3/MISO1/MAT1.3)P0.18_53") (pintype "bidirectional"))
    )
    (net (code "55") (name "unconnected-(U401-(DTR1{slash}MAT1.1{slash}AD1.4)P0.13-Pad39)") (class "Default")
      (node (ref "U401") (pin "39") (pinfunction "(DTR1/MAT1.1/AD1.4)P0.13_39") (pintype "bidirectional"))
    )
    (net (code "56") (name "unconnected-(U401-(EINT0{slash}MAT0.2{slash}CAP0.2)P0.16-Pad46)") (class "Default")
      (node (ref "U401") (pin "46") (pinfunction "(EINT0/MAT0.2/CAP0.2)P0.16_46") (pintype "bidirectional"))
    )
    (net (code "57") (name "unconnected-(U401-(MAT1.2{slash}MOSI1{slash}CAP1.2)P0.19-Pad54)") (class "Default")
      (node (ref "U401") (pin "54") (pinfunction "(MAT1.2/MOSI1/CAP1.2)P0.19_54") (pintype "bidirectional"))
    )
    (net (code "58") (name "unconnected-(U401-(MAT1.3{slash}SSEL1{slash}EINT3)P0.20-Pad55)") (class "Default")
      (node (ref "U401") (pin "55") (pinfunction "(MAT1.3/SSEL1/EINT3)P0.20_55") (pintype "bidirectional"))
    )
    (net (code "59") (name "unconnected-(U401-(RI1{slash}EINT2{slash}AD1.5)P0.15-Pad45)") (class "Default")
      (node (ref "U401") (pin "45") (pinfunction "(RI1/EINT2/AD1.5)P0.15_45") (pintype "bidirectional"))
    )
    (net (code "60") (name "unconnected-(U401-D+-Pad10)") (class "Default")
      (node (ref "U401") (pin "10") (pinfunction "D+_10") (pintype "bidirectional"))
    )
    (net (code "61") (name "unconnected-(U401-D--Pad11)") (class "Default")
      (node (ref "U401") (pin "11") (pinfunction "D-_11") (pintype "bidirectional"))
    )
    (net (code "62") (name "unconnected-(U401-P0.23-Pad58)") (class "Default")
      (node (ref "U401") (pin "58") (pinfunction "P0.23_58") (pintype "bidirectional"))
    )
    (net (code "63") (name "unconnected-(U401-P0.31-Pad17)") (class "Default")
      (node (ref "U401") (pin "17") (pinfunction "P0.31_17") (pintype "output"))
    )
    (net (code "64") (name "unconnected-(U401-P1.16(TRACEPKT0)-Pad16)") (class "Default")
      (node (ref "U401") (pin "16") (pinfunction "P1.16(TRACEPKT0)_16") (pintype "bidirectional"))
    )
    (net (code "65") (name "unconnected-(U401-P1.17(TRACEPKT1)-Pad12)") (class "Default")
      (node (ref "U401") (pin "12") (pinfunction "P1.17(TRACEPKT1)_12") (pintype "bidirectional"))
    )
    (net (code "66") (name "unconnected-(U401-P1.18(TRACEPKT2)-Pad8)") (class "Default")
      (node (ref "U401") (pin "8") (pinfunction "P1.18(TRACEPKT2)_8") (pintype "bidirectional"))
    )
    (net (code "67") (name "unconnected-(U401-P1.19(TRACEPKT3)-Pad4)") (class "Default")
      (node (ref "U401") (pin "4") (pinfunction "P1.19(TRACEPKT3)_4") (pintype "bidirectional"))
    )
    (net (code "68") (name "unconnected-(U401-P1.20(TRACESYNC)-Pad48)") (class "Default")
      (node (ref "U401") (pin "48") (pinfunction "P1.20(TRACESYNC)_48") (pintype "bidirectional"))
    )
    (net (code "69") (name "unconnected-(U401-P1.21(PIPESTAT0)-Pad44)") (class "Default")
      (node (ref "U401") (pin "44") (pinfunction "P1.21(PIPESTAT0)_44") (pintype "bidirectional"))
    )
    (net (code "70") (name "unconnected-(U401-P1.22(PIPESTAT1)-Pad40)") (class "Default")
      (node (ref "U401") (pin "40") (pinfunction "P1.22(PIPESTAT1)_40") (pintype "bidirectional"))
    )
    (net (code "71") (name "unconnected-(U401-P1.23(PIPESTAT2)-Pad36)") (class "Default")
      (node (ref "U401") (pin "36") (pinfunction "P1.23(PIPESTAT2)_36") (pintype "bidirectional"))
    )
    (net (code "72") (name "unconnected-(U401-P1.25(EXTIN0)-Pad28)") (class "Default")
      (node (ref "U401") (pin "28") (pinfunction "P1.25(EXTIN0)_28") (pintype "bidirectional"))
    )
    (net (code "73") (name "unconnected-(U401-P1.26(RTCK)-Pad24)") (class "Default")
      (node (ref "U401") (pin "24") (pinfunction "P1.26(RTCK)_24") (pintype "bidirectional"))
    )
    (net (code "74") (name "unconnected-(U401-P1.27(TDO)-Pad64)") (class "Default")
      (node (ref "U401") (pin "64") (pinfunction "P1.27(TDO)_64") (pintype "bidirectional"))
    )
    (net (code "75") (name "unconnected-(U401-P1.28(TDI)-Pad60)") (class "Default")
      (node (ref "U401") (pin "60") (pinfunction "P1.28(TDI)_60") (pintype "bidirectional"))
    )
    (net (code "76") (name "unconnected-(U401-P1.29(TCK)-Pad56)") (class "Default")
      (node (ref "U401") (pin "56") (pinfunction "P1.29(TCK)_56") (pintype "bidirectional"))
    )
    (net (code "77") (name "unconnected-(U401-P1.30(TMS)-Pad52)") (class "Default")
      (node (ref "U401") (pin "52") (pinfunction "P1.30(TMS)_52") (pintype "bidirectional"))
    )
    (net (code "78") (name "unconnected-(U401-P1.31({slash}TRST)-Pad20)") (class "Default")
      (node (ref "U401") (pin "20") (pinfunction "P1.31(/TRST)_20") (pintype "bidirectional"))
    )
    (net (code "79") (name "unconnected-(U401-RTXC2-Pad5)") (class "Default")
      (node (ref "U401") (pin "5") (pinfunction "RTXC2_5") (pintype "output"))
    )
    (net (code "80") (name "unconnected-(U601-CLKOUT-Pad22)") (class "Default")
      (node (ref "U601") (pin "22") (pinfunction "CLKOUT_22") (pintype "bidirectional"))
    )
    (net (code "81") (name "unconnected-(U601-ES_CL-Pad7)") (class "Default")
      (node (ref "U601") (pin "7") (pinfunction "ES_CL_7") (pintype "bidirectional"))
    )
    (net (code "82") (name "unconnected-(U601-ES_DA-Pad6)") (class "Default")
      (node (ref "U601") (pin "6") (pinfunction "ES_DA_6") (pintype "bidirectional"))
    )
    (net (code "83") (name "unconnected-(U701-CD-PadCD1)") (class "Default")
      (node (ref "U701") (pin "CD1") (pinfunction "CD_CD1") (pintype "bidirectional"))
    )
    (net (code "84") (name "unconnected-(U701-NC-Pad1)") (class "Default")
      (node (ref "U701") (pin "1") (pinfunction "NC_1") (pintype "bidirectional"))
    )
    (net (code "85") (name "unconnected-(U701-RSV-Pad8)") (class "Default")
      (node (ref "U701") (pin "8") (pinfunction "RSV_8") (pintype "bidirectional"))
    )
  )
)
